# nixiRemoteControlReceiver.net
KiCad netlist of a schematic drawn in EAGLE
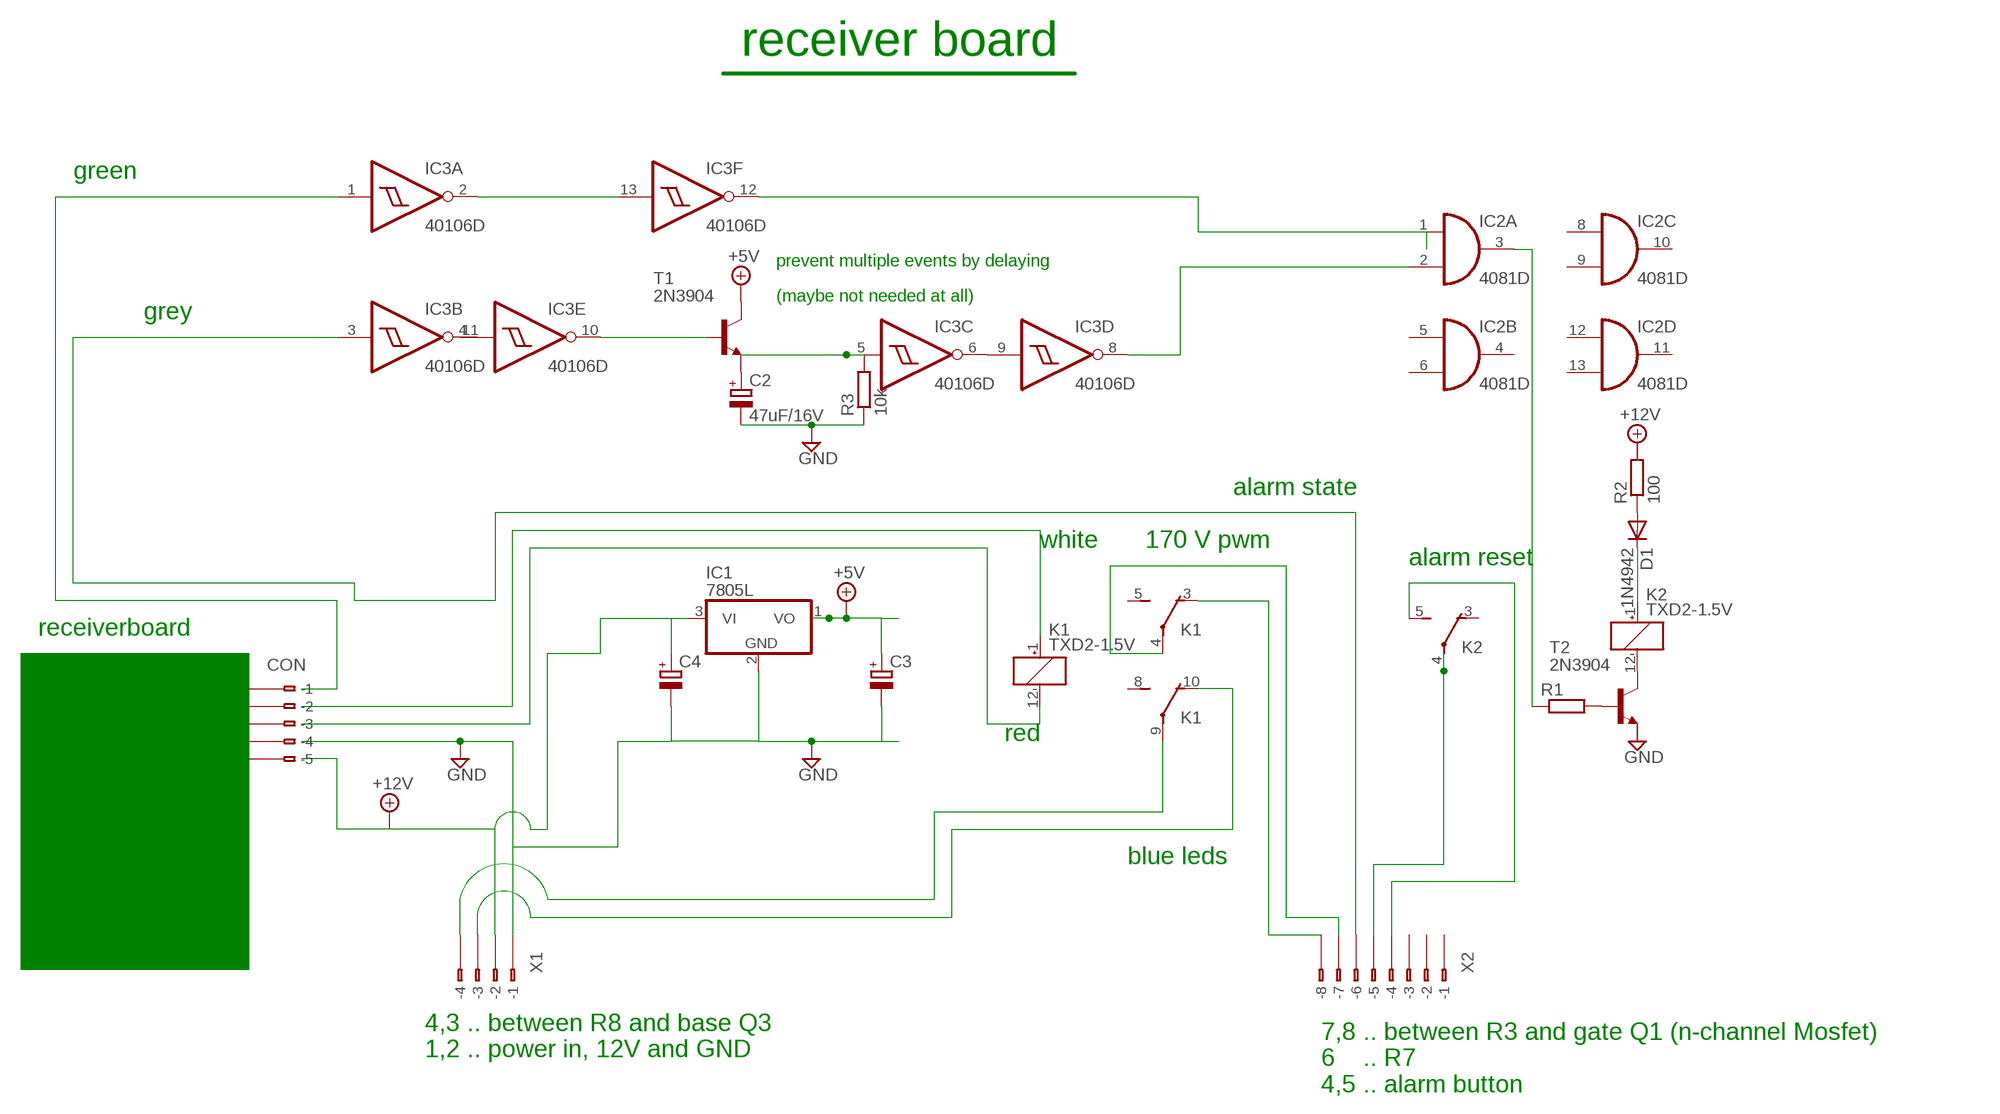
[diagram p0: schematic, sheet 1]

(export (version "E")
  (design (tool "Eeschema 10.0.6"))
  (components
    (comp (ref "C2")
      (value "47uF/16V")
      (footprint "eagle-import:EB20D")
      (libsource (lib "eagle-import") (part "CPOL-EUE10-20"))
    )
    (comp (ref "C3")
      (value "CPOL-EUE10-20")
      (footprint "eagle-import:EB20D")
      (libsource (lib "eagle-import") (part "CPOL-EUE10-20"))
    )
    (comp (ref "C4")
      (value "CPOL-EUE10-20")
      (footprint "eagle-import:EB20D")
      (libsource (lib "eagle-import") (part "CPOL-EUE10-20"))
    )
    (comp (ref "CON")
      (value "233-105")
      (footprint "eagle-import:233-105")
      (libsource (lib "eagle-import") (part "233-105"))
    )
    (comp (ref "D1")
      (value "1N4942")
      (footprint "eagle-import:DO41-10")
      (libsource (lib "eagle-import") (part "1N4942"))
    )
    (comp (ref "IC1")
      (value "7805L")
      (footprint "eagle-import:TO92")
      (libsource (lib "eagle-import") (part "78L05"))
    )
    (comp (ref "IC2")
      (value "4081D")
      (footprint "eagle-import:SO14")
      (libsource (lib "eagle-import") (part "4081D"))
    )
    (comp (ref "IC3")
      (value "40106D")
      (footprint "eagle-import:SO14")
      (libsource (lib "eagle-import") (part "40106D"))
    )
    (comp (ref "K1")
      (value "TXD2-1.5V")
      (footprint "eagle-import:TXD2")
      (libsource (lib "eagle-import") (part "TX?-D21.5V"))
    )
    (comp (ref "K2")
      (value "TXD2-1.5V")
      (footprint "eagle-import:TXD2")
      (libsource (lib "eagle-import") (part "TX?-D21.5V"))
    )
    (comp (ref "R1")
      (value "R-EU_0411/15")
      (footprint "eagle-import:0411_15")
      (libsource (lib "eagle-import") (part "R-EU_0411/15"))
    )
    (comp (ref "R2")
      (value "100")
      (footprint "eagle-import:0411_15")
      (libsource (lib "eagle-import") (part "R-EU_0411/15"))
    )
    (comp (ref "R3")
      (value "10k")
      (footprint "eagle-import:0411_15")
      (libsource (lib "eagle-import") (part "R-EU_0411/15"))
    )
    (comp (ref "T1")
      (value "2N3904")
      (footprint "eagle-import:TO92")
      (libsource (lib "eagle-import") (part "2N3904"))
    )
    (comp (ref "T2")
      (value "2N3904")
      (footprint "eagle-import:TO92")
      (libsource (lib "eagle-import") (part "2N3904"))
    )
    (comp (ref "X1")
      (value "233-104")
      (footprint "eagle-import:233-104")
      (libsource (lib "eagle-import") (part "233-104"))
    )
    (comp (ref "X2")
      (value "233-108")
      (footprint "eagle-import:233-108")
      (libsource (lib "eagle-import") (part "233-108"))
    )
  )
  (nets
    (net (code "1") (name "+5V") (class "Default")
      (node (ref "C3") (pin "+") (pinfunction "+_+") (pintype "passive"))
      (node (ref "IC1") (pin "1") (pinfunction "VO_1") (pintype "passive"))
      (node (ref "T1") (pin "1") (pinfunction "C_1") (pintype "passive"))
    )
    (net (code "2") (name "+12V") (class "Default")
      (node (ref "C4") (pin "+") (pinfunction "+_+") (pintype "passive"))
      (node (ref "IC1") (pin "3") (pinfunction "VI_3") (pintype "input"))
      (node (ref "R2") (pin "2") (pinfunction "2_2") (pintype "passive"))
      (node (ref "X1") (pin "B2") (pinfunction "B-2_B2") (pintype "passive"))
    )
    (net (code "3") (name "GND") (class "Default")
      (node (ref "C2") (pin "-") (pinfunction "-_-") (pintype "passive"))
      (node (ref "C3") (pin "-") (pinfunction "-_-") (pintype "passive"))
      (node (ref "C4") (pin "-") (pinfunction "-_-") (pintype "passive"))
      (node (ref "IC1") (pin "2") (pinfunction "GND_2") (pintype "passive"))
      (node (ref "R3") (pin "1") (pinfunction "1_1") (pintype "passive"))
      (node (ref "T2") (pin "3") (pinfunction "E_3") (pintype "passive"))
      (node (ref "X1") (pin "B1") (pinfunction "B-1_B1") (pintype "passive"))
    )
    (net (code "4") (name "Net-(D1-PadA)") (class "Default")
      (node (ref "D1") (pin "A") (pinfunction "A_A") (pintype "passive"))
      (node (ref "R2") (pin "1") (pinfunction "1_1") (pintype "passive"))
    )
    (net (code "5") (name "Net-(IC2A-I1)") (class "Default")
      (node (ref "IC2") (pin "2") (pinfunction "I1_2") (pintype "input"))
      (node (ref "IC3") (pin "8") (pinfunction "O_8") (pintype "output"))
    )
    (net (code "6") (name "Net-(IC2A-O)") (class "Default")
      (node (ref "IC2") (pin "3") (pinfunction "O_3") (pintype "output"))
      (node (ref "R1") (pin "1") (pinfunction "1_1") (pintype "passive"))
    )
    (net (code "7") (name "Net-(IC3A-O)") (class "Default")
      (node (ref "IC3") (pin "13") (pinfunction "I_13") (pintype "input"))
      (node (ref "IC3") (pin "2") (pinfunction "O_2") (pintype "output"))
    )
    (net (code "8") (name "Net-(IC3B-I)") (class "Default")
      (node (ref "IC3") (pin "3") (pinfunction "I_3") (pintype "input"))
      (node (ref "X2") (pin "B6") (pinfunction "B-6_B6") (pintype "passive"))
    )
    (net (code "9") (name "Net-(IC3C-I)") (class "Default")
      (node (ref "IC3") (pin "5") (pinfunction "I_5") (pintype "input"))
      (node (ref "R3") (pin "2") (pinfunction "2_2") (pintype "passive"))
    )
    (net (code "10") (name "Net-(IC3C-O)") (class "Default")
      (node (ref "IC3") (pin "6") (pinfunction "O_6") (pintype "output"))
      (node (ref "IC3") (pin "9") (pinfunction "I_9") (pintype "input"))
    )
    (net (code "11") (name "Net-(IC3E-O)") (class "Default")
      (node (ref "IC3") (pin "10") (pinfunction "O_10") (pintype "output"))
      (node (ref "T1") (pin "2") (pinfunction "B_2") (pintype "passive"))
    )
    (net (code "12") (name "Net-(K1A-O)") (class "Default")
      (node (ref "K1") (pin "3") (pinfunction "O_3") (pintype "passive"))
      (node (ref "X2") (pin "B8") (pinfunction "B-8_B8") (pintype "passive"))
    )
    (net (code "13") (name "Net-(K1A-P)") (class "Default")
      (node (ref "K1") (pin "4") (pinfunction "P_4") (pintype "passive"))
      (node (ref "X2") (pin "B7") (pinfunction "B-7_B7") (pintype "passive"))
    )
    (net (code "14") (name "Net-(K1B-O)") (class "Default")
      (node (ref "K1") (pin "10") (pinfunction "O_10") (pintype "passive"))
      (node (ref "X1") (pin "B3") (pinfunction "B-3_B3") (pintype "passive"))
    )
    (net (code "15") (name "Net-(K1B-P)") (class "Default")
      (node (ref "K1") (pin "9") (pinfunction "P_9") (pintype "passive"))
      (node (ref "X1") (pin "B4") (pinfunction "B-4_B4") (pintype "passive"))
    )
    (net (code "16") (name "Net-(K2A-P)") (class "Default")
      (node (ref "K2") (pin "4") (pinfunction "P_4") (pintype "passive"))
      (node (ref "X2") (pin "B5") (pinfunction "B-5_B5") (pintype "passive"))
    )
    (net (code "17") (name "Net-(K2A-S)") (class "Default")
      (node (ref "K2") (pin "5") (pinfunction "S_5") (pintype "passive"))
      (node (ref "X2") (pin "B4") (pinfunction "B-4_B4") (pintype "passive"))
    )
    (net (code "18") (name "Net-(K2C-+)") (class "Default")
      (node (ref "D1") (pin "C") (pinfunction "C_C") (pintype "passive"))
      (node (ref "K2") (pin "1") (pinfunction "+_1") (pintype "passive"))
    )
    (net (code "19") (name "Net-(K2C--)") (class "Default")
      (node (ref "K2") (pin "12") (pinfunction "-_12") (pintype "passive"))
      (node (ref "T2") (pin "1") (pinfunction "C_1") (pintype "passive"))
    )
    (net (code "20") (name "Net-(T1-E)") (class "Default")
      (node (ref "C2") (pin "+") (pinfunction "+_+") (pintype "passive"))
      (node (ref "T1") (pin "3") (pinfunction "E_3") (pintype "passive"))
    )
    (net (code "21") (name "Net-(T2-B)") (class "Default")
      (node (ref "R1") (pin "2") (pinfunction "2_2") (pintype "passive"))
      (node (ref "T2") (pin "2") (pinfunction "B_2") (pintype "passive"))
    )
    (net (code "22") (name "unconnected-(CON--1-PadA1)") (class "Default")
      (node (ref "CON") (pin "A1") (pinfunction "-1_A1") (pintype "passive"))
    )
    (net (code "23") (name "unconnected-(CON--2-PadA2)") (class "Default")
      (node (ref "CON") (pin "A2") (pinfunction "-2_A2") (pintype "passive"))
    )
    (net (code "24") (name "unconnected-(CON--3-PadA3)") (class "Default")
      (node (ref "CON") (pin "A3") (pinfunction "-3_A3") (pintype "passive"))
    )
    (net (code "25") (name "unconnected-(CON--4-PadA4)") (class "Default")
      (node (ref "CON") (pin "A4") (pinfunction "-4_A4") (pintype "passive"))
    )
    (net (code "26") (name "unconnected-(CON--5-PadA5)") (class "Default")
      (node (ref "CON") (pin "A5") (pinfunction "-5_A5") (pintype "passive"))
    )
    (net (code "27") (name "unconnected-(CON-B-1-PadB1)") (class "Default")
      (node (ref "CON") (pin "B1") (pinfunction "B-1_B1") (pintype "passive"))
    )
    (net (code "28") (name "unconnected-(CON-B-2-PadB2)") (class "Default")
      (node (ref "CON") (pin "B2") (pinfunction "B-2_B2") (pintype "passive"))
    )
    (net (code "29") (name "unconnected-(CON-B-3-PadB3)") (class "Default")
      (node (ref "CON") (pin "B3") (pinfunction "B-3_B3") (pintype "passive"))
    )
    (net (code "30") (name "unconnected-(CON-B-4-PadB4)") (class "Default")
      (node (ref "CON") (pin "B4") (pinfunction "B-4_B4") (pintype "passive"))
    )
    (net (code "31") (name "unconnected-(CON-B-5-PadB5)") (class "Default")
      (node (ref "CON") (pin "B5") (pinfunction "B-5_B5") (pintype "passive"))
    )
    (net (code "32") (name "unconnected-(IC2A-I0-Pad1)") (class "Default")
      (node (ref "IC2") (pin "1") (pinfunction "I0_1") (pintype "input"))
    )
    (net (code "33") (name "unconnected-(IC2B-I0-Pad5)") (class "Default")
      (node (ref "IC2") (pin "5") (pinfunction "I0_5") (pintype "input"))
    )
    (net (code "34") (name "unconnected-(IC2B-I1-Pad6)") (class "Default")
      (node (ref "IC2") (pin "6") (pinfunction "I1_6") (pintype "input"))
    )
    (net (code "35") (name "unconnected-(IC2B-O-Pad4)") (class "Default")
      (node (ref "IC2") (pin "4") (pinfunction "O_4") (pintype "output"))
    )
    (net (code "36") (name "unconnected-(IC2C-I0-Pad8)") (class "Default")
      (node (ref "IC2") (pin "8") (pinfunction "I0_8") (pintype "input"))
    )
    (net (code "37") (name "unconnected-(IC2C-I1-Pad9)") (class "Default")
      (node (ref "IC2") (pin "9") (pinfunction "I1_9") (pintype "input"))
    )
    (net (code "38") (name "unconnected-(IC2C-O-Pad10)") (class "Default")
      (node (ref "IC2") (pin "10") (pinfunction "O_10") (pintype "output"))
    )
    (net (code "39") (name "unconnected-(IC2D-I0-Pad12)") (class "Default")
      (node (ref "IC2") (pin "12") (pinfunction "I0_12") (pintype "input"))
    )
    (net (code "40") (name "unconnected-(IC2D-I1-Pad13)") (class "Default")
      (node (ref "IC2") (pin "13") (pinfunction "I1_13") (pintype "input"))
    )
    (net (code "41") (name "unconnected-(IC2D-O-Pad11)") (class "Default")
      (node (ref "IC2") (pin "11") (pinfunction "O_11") (pintype "output"))
    )
    (net (code "42") (name "unconnected-(IC3A-I-Pad1)") (class "Default")
      (node (ref "IC3") (pin "1") (pinfunction "I_1") (pintype "input"))
    )
    (net (code "43") (name "unconnected-(IC3B-O-Pad4)") (class "Default")
      (node (ref "IC3") (pin "4") (pinfunction "O_4") (pintype "output"))
    )
    (net (code "44") (name "unconnected-(IC3E-I-Pad11)") (class "Default")
      (node (ref "IC3") (pin "11") (pinfunction "I_11") (pintype "input"))
    )
    (net (code "45") (name "unconnected-(IC3F-O-Pad12)") (class "Default")
      (node (ref "IC3") (pin "12") (pinfunction "O_12") (pintype "output"))
    )
    (net (code "46") (name "unconnected-(K1A-S-Pad5)") (class "Default")
      (node (ref "K1") (pin "5") (pinfunction "S_5") (pintype "passive"))
    )
    (net (code "47") (name "unconnected-(K1B-S-Pad8)") (class "Default")
      (node (ref "K1") (pin "8") (pinfunction "S_8") (pintype "passive"))
    )
    (net (code "48") (name "unconnected-(K1C-+-Pad1)") (class "Default")
      (node (ref "K1") (pin "1") (pinfunction "+_1") (pintype "passive"))
    )
    (net (code "49") (name "unconnected-(K1C---Pad12)") (class "Default")
      (node (ref "K1") (pin "12") (pinfunction "-_12") (pintype "passive"))
    )
    (net (code "50") (name "unconnected-(K2A-O-Pad3)") (class "Default")
      (node (ref "K2") (pin "3") (pinfunction "O_3") (pintype "passive"))
    )
    (net (code "51") (name "unconnected-(X1--1-PadA1)") (class "Default")
      (node (ref "X1") (pin "A1") (pinfunction "-1_A1") (pintype "passive"))
    )
    (net (code "52") (name "unconnected-(X1--2-PadA2)") (class "Default")
      (node (ref "X1") (pin "A2") (pinfunction "-2_A2") (pintype "passive"))
    )
    (net (code "53") (name "unconnected-(X1--3-PadA3)") (class "Default")
      (node (ref "X1") (pin "A3") (pinfunction "-3_A3") (pintype "passive"))
    )
    (net (code "54") (name "unconnected-(X1--4-PadA4)") (class "Default")
      (node (ref "X1") (pin "A4") (pinfunction "-4_A4") (pintype "passive"))
    )
    (net (code "55") (name "unconnected-(X2--1-PadA1)") (class "Default")
      (node (ref "X2") (pin "A1") (pinfunction "-1_A1") (pintype "passive"))
    )
    (net (code "56") (name "unconnected-(X2--2-PadA2)") (class "Default")
      (node (ref "X2") (pin "A2") (pinfunction "-2_A2") (pintype "passive"))
    )
    (net (code "57") (name "unconnected-(X2--3-PadA3)") (class "Default")
      (node (ref "X2") (pin "A3") (pinfunction "-3_A3") (pintype "passive"))
    )
    (net (code "58") (name "unconnected-(X2--4-PadA4)") (class "Default")
      (node (ref "X2") (pin "A4") (pinfunction "-4_A4") (pintype "passive"))
    )
    (net (code "59") (name "unconnected-(X2--5-PadA5)") (class "Default")
      (node (ref "X2") (pin "A5") (pinfunction "-5_A5") (pintype "passive"))
    )
    (net (code "60") (name "unconnected-(X2--6-PadA6)") (class "Default")
      (node (ref "X2") (pin "A6") (pinfunction "-6_A6") (pintype "passive"))
    )
    (net (code "61") (name "unconnected-(X2--7-PadA7)") (class "Default")
      (node (ref "X2") (pin "A7") (pinfunction "-7_A7") (pintype "passive"))
    )
    (net (code "62") (name "unconnected-(X2--8-PadA8)") (class "Default")
      (node (ref "X2") (pin "A8") (pinfunction "-8_A8") (pintype "passive"))
    )
    (net (code "63") (name "unconnected-(X2-B-1-PadB1)") (class "Default")
      (node (ref "X2") (pin "B1") (pinfunction "B-1_B1") (pintype "passive"))
    )
    (net (code "64") (name "unconnected-(X2-B-2-PadB2)") (class "Default")
      (node (ref "X2") (pin "B2") (pinfunction "B-2_B2") (pintype "passive"))
    )
    (net (code "65") (name "unconnected-(X2-B-3-PadB3)") (class "Default")
      (node (ref "X2") (pin "B3") (pinfunction "B-3_B3") (pintype "passive"))
    )
  )
)
